# Receiver.net
KiCad netlist of a schematic drawn in EAGLE
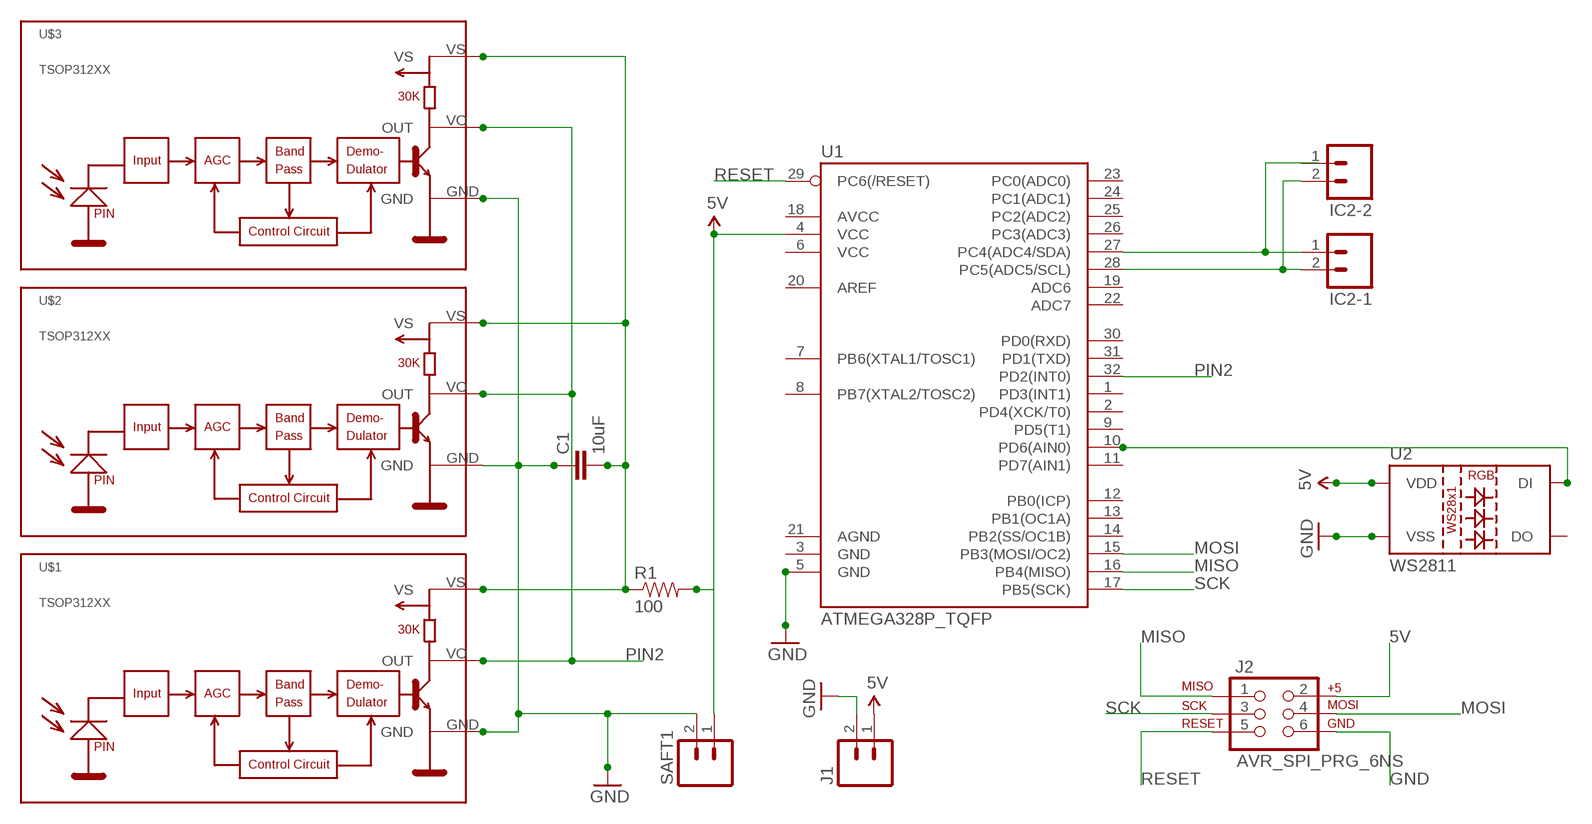
[diagram p0: schematic, sheet 1]

(export (version "E")
  (design (tool "Eeschema 10.0.6"))
  (components
    (comp (ref "C1")
      (value "10uF")
      (footprint "eagle-import:0603-CAP")
      (libsource (lib "eagle-import") (part "10UF-6.3V-20%(0603)"))
    )
    (comp (ref "IC2-1")
      (value "M02-JST-2-PTH-NO_SILK")
      (footprint "eagle-import:JST-2-PTH-NS")
      (libsource (lib "eagle-import") (part "M02-JST-2-PTH-NO_SILK"))
    )
    (comp (ref "IC2-2")
      (value "M02-JST-2-PTH-NO_SILK")
      (footprint "eagle-import:JST-2-PTH-NS")
      (libsource (lib "eagle-import") (part "M02-JST-2-PTH-NO_SILK"))
    )
    (comp (ref "J1")
      (value "M02-JST-2-PTH-NO_SILK")
      (footprint "eagle-import:JST-2-PTH-NS")
      (libsource (lib "eagle-import") (part "M02-JST-2-PTH-NO_SILK"))
    )
    (comp (ref "J2")
      (value "AVR_SPI_PRG_6NS")
      (footprint "eagle-import:2X3-NS")
      (libsource (lib "eagle-import") (part "AVR_SPI_PRG_6NS"))
    )
    (comp (ref "R1")
      (value "100")
      (footprint "eagle-import:0603-RES")
      (libsource (lib "eagle-import") (part "RESISTOR0603"))
    )
    (comp (ref "SAFT1")
      (value "M02-JST-2-PTH-NO_SILK")
      (footprint "eagle-import:JST-2-PTH-NS")
      (libsource (lib "eagle-import") (part "M02-JST-2-PTH-NO_SILK"))
    )
    (comp (ref "U$1")
      (value "TSOP312XX")
      (footprint "eagle-import:TSOP312")
      (libsource (lib "eagle-import") (part "TSOP312XX"))
    )
    (comp (ref "U$2")
      (value "TSOP312XX")
      (footprint "eagle-import:TSOP312")
      (libsource (lib "eagle-import") (part "TSOP312XX"))
    )
    (comp (ref "U$3")
      (value "TSOP312XX")
      (footprint "eagle-import:TSOP312")
      (libsource (lib "eagle-import") (part "TSOP312XX"))
    )
    (comp (ref "U1")
      (value "ATMEGA328P_TQFP")
      (footprint "eagle-import:TQFP32-08")
      (libsource (lib "eagle-import") (part "ATMEGA328P_TQFP"))
    )
    (comp (ref "U2")
      (value "WS2811")
      (footprint "eagle-import:LED-TRICOLOR-5050-IC")
      (libsource (lib "eagle-import") (part "LED-TRICOLOR-5050-ICWS2811"))
    )
  )
  (nets
    (net (code "1") (name "/MISO") (class "Default")
      (node (ref "J2") (pin "1") (pinfunction "1_1") (pintype "passive"))
      (node (ref "U1") (pin "16") (pinfunction "PB4(MISO)_16") (pintype "bidirectional"))
    )
    (net (code "2") (name "/MOSI") (class "Default")
      (node (ref "J2") (pin "4") (pinfunction "4_4") (pintype "passive"))
      (node (ref "U1") (pin "15") (pinfunction "PB3(MOSI/OC2)_15") (pintype "bidirectional"))
    )
    (net (code "3") (name "/PIN2") (class "Default")
      (node (ref "U$1") (pin "VO") (pinfunction "OUT_VO") (pintype "output"))
      (node (ref "U$2") (pin "VO") (pinfunction "OUT_VO") (pintype "output"))
      (node (ref "U$3") (pin "VO") (pinfunction "OUT_VO") (pintype "output"))
      (node (ref "U1") (pin "32") (pinfunction "PD2(INT0)_32") (pintype "bidirectional"))
    )
    (net (code "4") (name "/RESET") (class "Default")
      (node (ref "J2") (pin "5") (pinfunction "5_5") (pintype "passive"))
      (node (ref "U1") (pin "29") (pinfunction "PC6(/RESET)_29") (pintype "bidirectional"))
    )
    (net (code "5") (name "/SCK") (class "Default")
      (node (ref "J2") (pin "3") (pinfunction "3_3") (pintype "passive"))
      (node (ref "U1") (pin "17") (pinfunction "PB5(SCK)_17") (pintype "bidirectional"))
    )
    (net (code "6") (name "5V") (class "Default")
      (node (ref "J1") (pin "1") (pinfunction "1_1") (pintype "passive"))
      (node (ref "J2") (pin "2") (pinfunction "2_2") (pintype "passive"))
      (node (ref "R1") (pin "2") (pinfunction "2_2") (pintype "passive"))
      (node (ref "SAFT1") (pin "1") (pinfunction "1_1") (pintype "passive"))
      (node (ref "U1") (pin "4") (pinfunction "VCC_4") (pintype "bidirectional"))
      (node (ref "U2") (pin "3") (pinfunction "VDD_3") (pintype "bidirectional"))
      (node (ref "U2") (pin "5") (pinfunction "VDD_5") (pintype "bidirectional"))
    )
    (net (code "7") (name "GND") (class "Default")
      (node (ref "C1") (pin "1") (pinfunction "1_1") (pintype "passive"))
      (node (ref "J1") (pin "2") (pinfunction "2_2") (pintype "passive"))
      (node (ref "J2") (pin "6") (pinfunction "6_6") (pintype "passive"))
      (node (ref "SAFT1") (pin "2") (pinfunction "2_2") (pintype "passive"))
      (node (ref "U$1") (pin "GND") (pinfunction "GND_GND") (pintype "power_in"))
      (node (ref "U$2") (pin "GND") (pinfunction "GND_GND") (pintype "power_in"))
      (node (ref "U$3") (pin "GND") (pinfunction "GND_GND") (pintype "power_in"))
      (node (ref "U1") (pin "5") (pinfunction "GND_5") (pintype "bidirectional"))
      (node (ref "U2") (pin "6") (pinfunction "VSS_6") (pintype "bidirectional"))
    )
    (net (code "8") (name "Net-(C1-Pad2)") (class "Default")
      (node (ref "C1") (pin "2") (pinfunction "2_2") (pintype "passive"))
      (node (ref "R1") (pin "1") (pinfunction "1_1") (pintype "passive"))
      (node (ref "U$1") (pin "VS") (pinfunction "VS_VS") (pintype "power_in"))
      (node (ref "U$2") (pin "VS") (pinfunction "VS_VS") (pintype "power_in"))
      (node (ref "U$3") (pin "VS") (pinfunction "VS_VS") (pintype "power_in"))
    )
    (net (code "9") (name "Net-(U1-PC4(ADC4{slash}SDA))") (class "Default")
      (node (ref "IC2-1") (pin "1") (pinfunction "1_1") (pintype "passive"))
      (node (ref "U1") (pin "27") (pinfunction "PC4(ADC4/SDA)_27") (pintype "bidirectional"))
    )
    (net (code "10") (name "Net-(U1-PC5(ADC5{slash}SCL))") (class "Default")
      (node (ref "IC2-1") (pin "2") (pinfunction "2_2") (pintype "passive"))
      (node (ref "IC2-2") (pin "2") (pinfunction "2_2") (pintype "passive"))
      (node (ref "U1") (pin "28") (pinfunction "PC5(ADC5/SCL)_28") (pintype "bidirectional"))
    )
    (net (code "11") (name "Net-(U1-PD6(AIN0))") (class "Default")
      (node (ref "U1") (pin "10") (pinfunction "PD6(AIN0)_10") (pintype "bidirectional"))
      (node (ref "U2") (pin "2") (pinfunction "DI_2") (pintype "bidirectional"))
    )
    (net (code "12") (name "unconnected-(IC2-2-Pad1)") (class "Default")
      (node (ref "IC2-2") (pin "1") (pinfunction "1_1") (pintype "passive"))
    )
    (net (code "13") (name "unconnected-(U1-ADC6-Pad19)") (class "Default")
      (node (ref "U1") (pin "19") (pinfunction "ADC6_19") (pintype "bidirectional"))
    )
    (net (code "14") (name "unconnected-(U1-ADC7-Pad22)") (class "Default")
      (node (ref "U1") (pin "22") (pinfunction "ADC7_22") (pintype "bidirectional"))
    )
    (net (code "15") (name "unconnected-(U1-AGND-Pad21)") (class "Default")
      (node (ref "U1") (pin "21") (pinfunction "AGND_21") (pintype "bidirectional"))
    )
    (net (code "16") (name "unconnected-(U1-AREF-Pad20)") (class "Default")
      (node (ref "U1") (pin "20") (pinfunction "AREF_20") (pintype "bidirectional"))
    )
    (net (code "17") (name "unconnected-(U1-AVCC-Pad18)") (class "Default")
      (node (ref "U1") (pin "18") (pinfunction "AVCC_18") (pintype "bidirectional"))
    )
    (net (code "18") (name "unconnected-(U1-GND-Pad3)") (class "Default")
      (node (ref "U1") (pin "3") (pinfunction "GND_3") (pintype "bidirectional"))
    )
    (net (code "19") (name "unconnected-(U1-PB0(ICP)-Pad12)") (class "Default")
      (node (ref "U1") (pin "12") (pinfunction "PB0(ICP)_12") (pintype "bidirectional"))
    )
    (net (code "20") (name "unconnected-(U1-PB1(OC1A)-Pad13)") (class "Default")
      (node (ref "U1") (pin "13") (pinfunction "PB1(OC1A)_13") (pintype "bidirectional"))
    )
    (net (code "21") (name "unconnected-(U1-PB2(SS{slash}OC1B)-Pad14)") (class "Default")
      (node (ref "U1") (pin "14") (pinfunction "PB2(SS/OC1B)_14") (pintype "bidirectional"))
    )
    (net (code "22") (name "unconnected-(U1-PB6(XTAL1{slash}TOSC1)-Pad7)") (class "Default")
      (node (ref "U1") (pin "7") (pinfunction "PB6(XTAL1/TOSC1)_7") (pintype "bidirectional"))
    )
    (net (code "23") (name "unconnected-(U1-PB7(XTAL2{slash}TOSC2)-Pad8)") (class "Default")
      (node (ref "U1") (pin "8") (pinfunction "PB7(XTAL2/TOSC2)_8") (pintype "bidirectional"))
    )
    (net (code "24") (name "unconnected-(U1-PC0(ADC0)-Pad23)") (class "Default")
      (node (ref "U1") (pin "23") (pinfunction "PC0(ADC0)_23") (pintype "bidirectional"))
    )
    (net (code "25") (name "unconnected-(U1-PC1(ADC1)-Pad24)") (class "Default")
      (node (ref "U1") (pin "24") (pinfunction "PC1(ADC1)_24") (pintype "bidirectional"))
    )
    (net (code "26") (name "unconnected-(U1-PC2(ADC2)-Pad25)") (class "Default")
      (node (ref "U1") (pin "25") (pinfunction "PC2(ADC2)_25") (pintype "bidirectional"))
    )
    (net (code "27") (name "unconnected-(U1-PC3(ADC3)-Pad26)") (class "Default")
      (node (ref "U1") (pin "26") (pinfunction "PC3(ADC3)_26") (pintype "bidirectional"))
    )
    (net (code "28") (name "unconnected-(U1-PD0(RXD)-Pad30)") (class "Default")
      (node (ref "U1") (pin "30") (pinfunction "PD0(RXD)_30") (pintype "bidirectional"))
    )
    (net (code "29") (name "unconnected-(U1-PD1(TXD)-Pad31)") (class "Default")
      (node (ref "U1") (pin "31") (pinfunction "PD1(TXD)_31") (pintype "bidirectional"))
    )
    (net (code "30") (name "unconnected-(U1-PD3(INT1)-Pad1)") (class "Default")
      (node (ref "U1") (pin "1") (pinfunction "PD3(INT1)_1") (pintype "bidirectional"))
    )
    (net (code "31") (name "unconnected-(U1-PD4(XCK{slash}T0)-Pad2)") (class "Default")
      (node (ref "U1") (pin "2") (pinfunction "PD4(XCK/T0)_2") (pintype "bidirectional"))
    )
    (net (code "32") (name "unconnected-(U1-PD5(T1)-Pad9)") (class "Default")
      (node (ref "U1") (pin "9") (pinfunction "PD5(T1)_9") (pintype "bidirectional"))
    )
    (net (code "33") (name "unconnected-(U1-PD7(AIN1)-Pad11)") (class "Default")
      (node (ref "U1") (pin "11") (pinfunction "PD7(AIN1)_11") (pintype "bidirectional"))
    )
    (net (code "34") (name "unconnected-(U1-VCC-Pad6)") (class "Default")
      (node (ref "U1") (pin "6") (pinfunction "VCC_6") (pintype "bidirectional"))
    )
    (net (code "35") (name "unconnected-(U2-DO-Pad1)") (class "Default")
      (node (ref "U2") (pin "1") (pinfunction "DO_1") (pintype "bidirectional"))
    )
  )
)
